# PMSM_500W_Controller_DC.net
KiCad netlist of a schematic drawn in Altium Designer
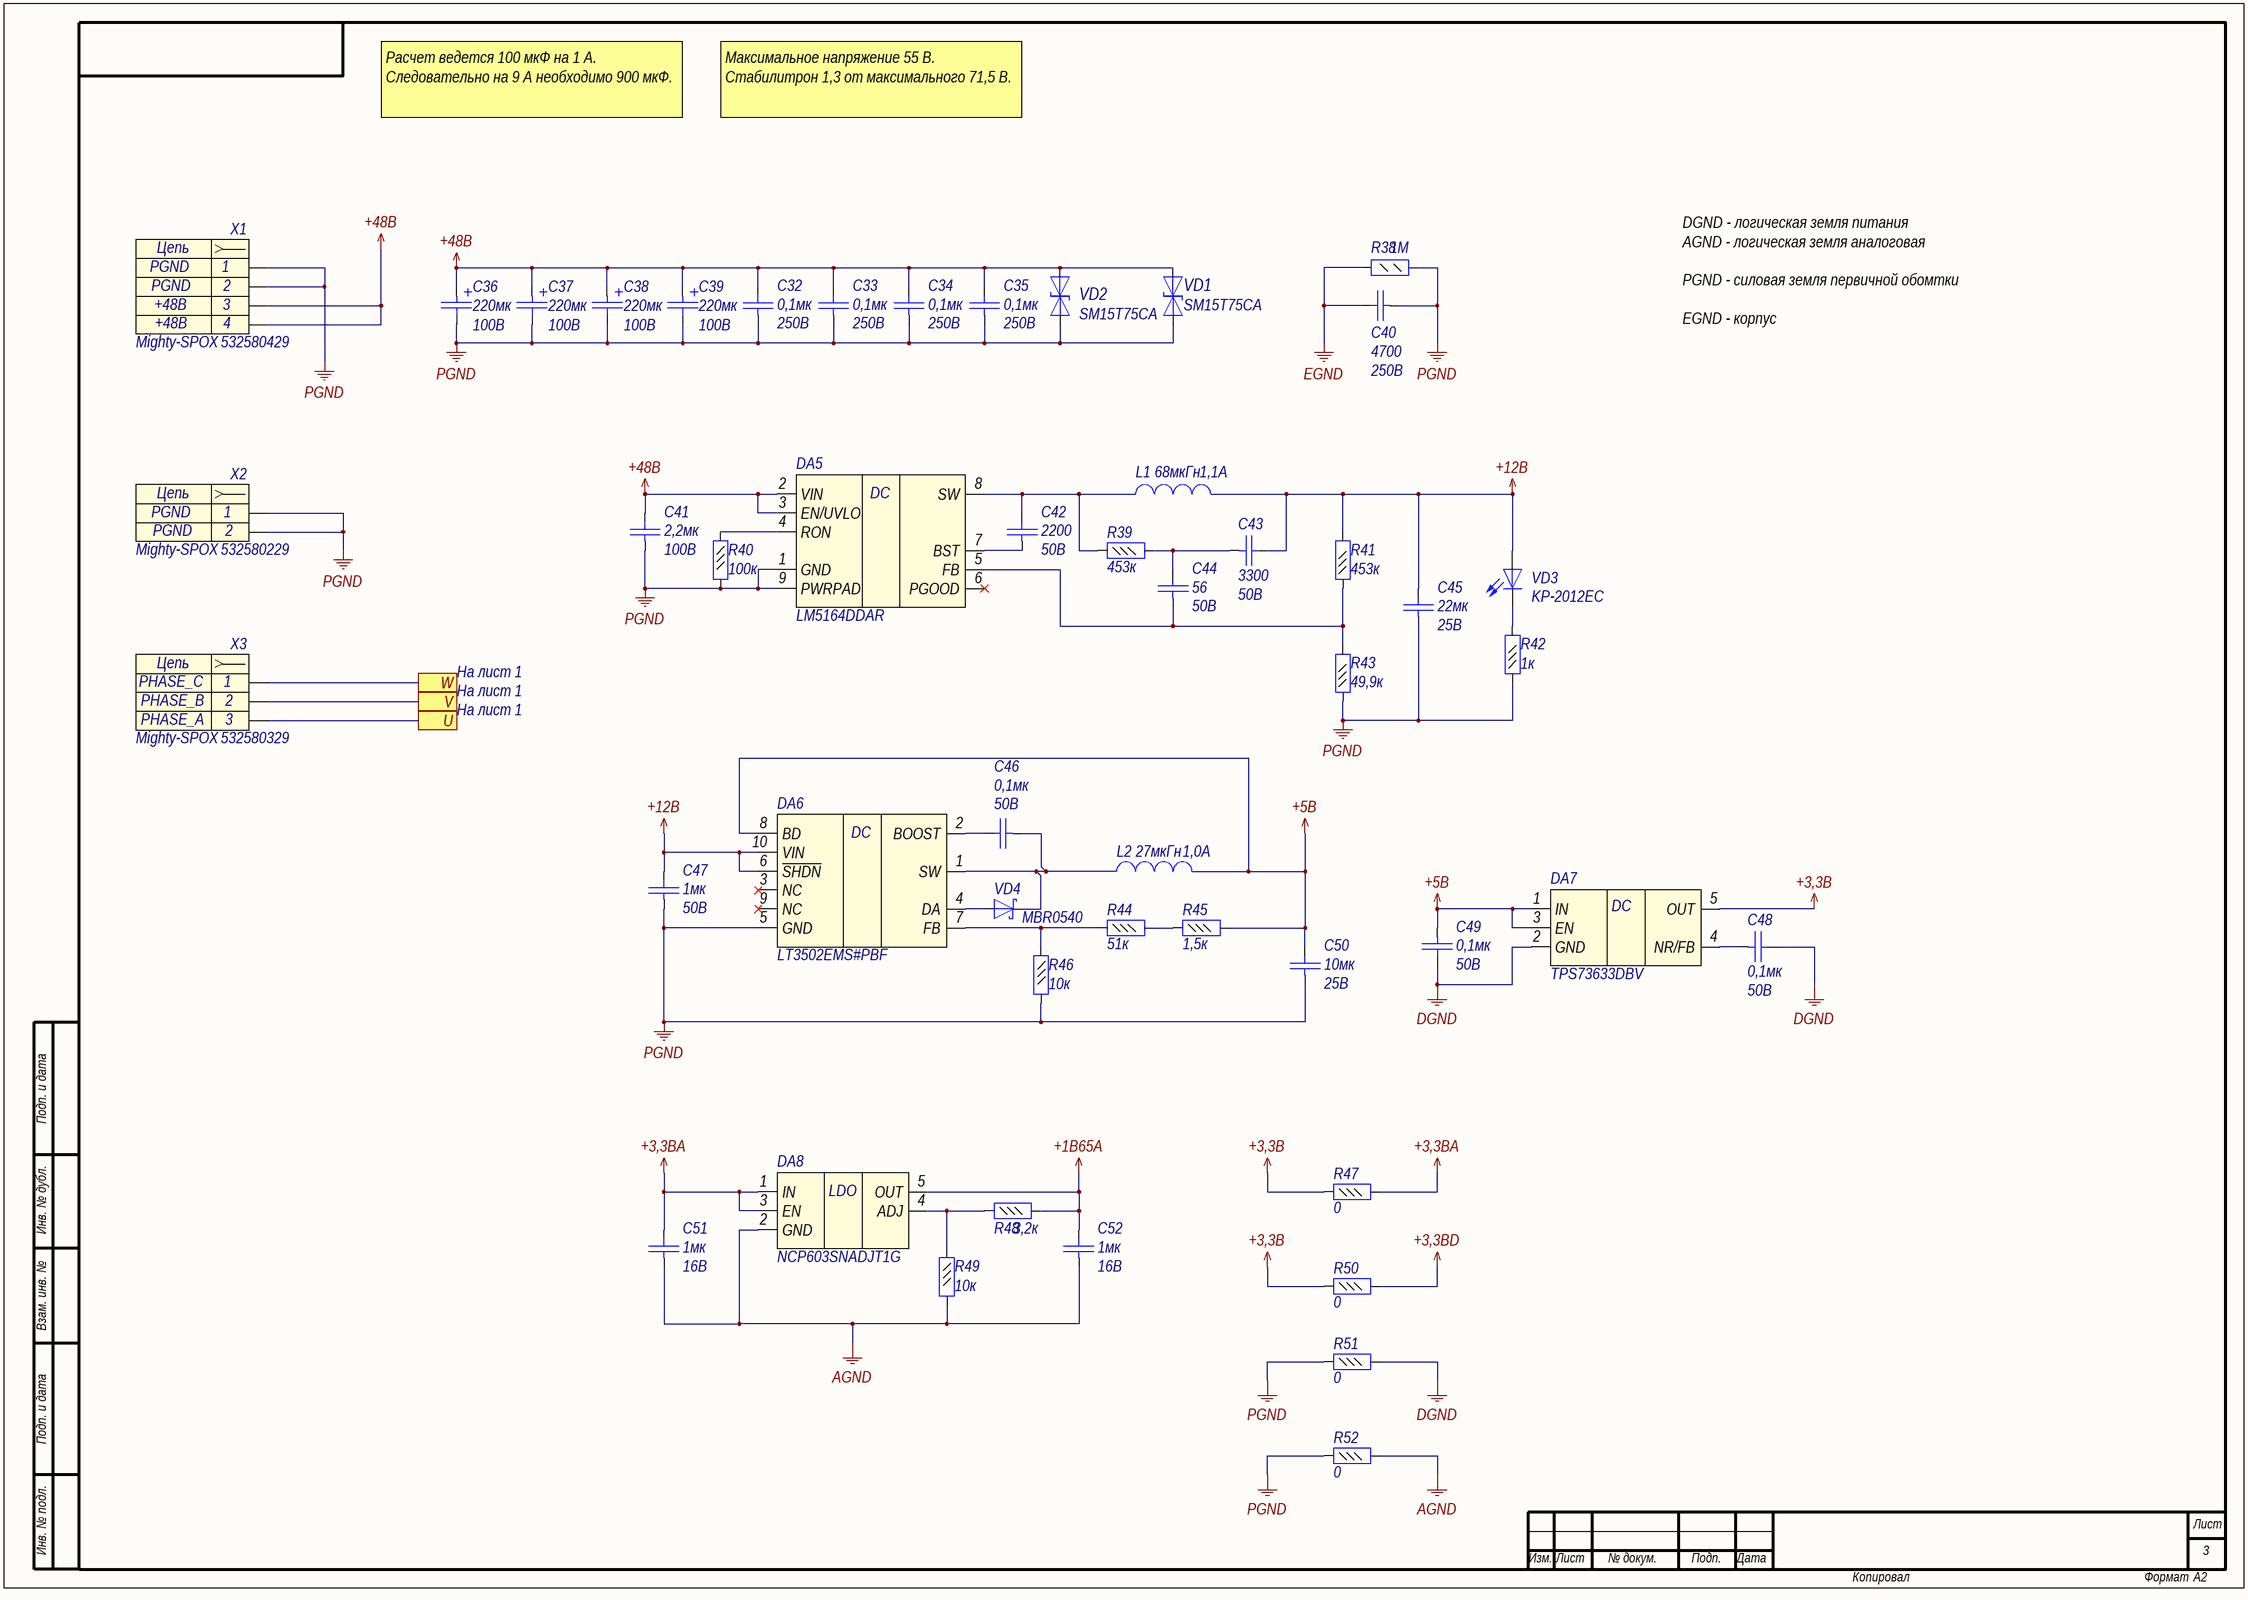
[diagram p0: PMSM_500W_Controller_DC.SchDoc]

(export (version "E")
  (design (tool "Eeschema 10.0.6"))
  (components
    (comp (ref "C32")
      (value "0,1мк")
      (footprint "C1206")
      (description "Конденсатор")
      (fields
        (field (name "VOLTAGE") "250В")
        (field (name "PART NUMBER") "GRM31CR72E104K")
        (field (name "Comment") "Capacitor")
      )
      (libsource (lib "MOP44") (part "Capacitor"))
    )
    (comp (ref "C33")
      (value "0,1мк")
      (footprint "C1206")
      (description "Конденсатор")
      (fields
        (field (name "VOLTAGE") "250В")
        (field (name "PART NUMBER") "GRM31CR72E104K")
        (field (name "Comment") "Capacitor")
      )
      (libsource (lib "MOP44") (part "Capacitor"))
    )
    (comp (ref "C34")
      (value "0,1мк")
      (footprint "C1206")
      (description "Конденсатор")
      (fields
        (field (name "VOLTAGE") "250В")
        (field (name "PART NUMBER") "GRM31CR72E104K")
        (field (name "Comment") "Capacitor")
      )
      (libsource (lib "MOP44") (part "Capacitor"))
    )
    (comp (ref "C35")
      (value "0,1мк")
      (footprint "C1206")
      (description "Конденсатор")
      (fields
        (field (name "VOLTAGE") "250В")
        (field (name "PART NUMBER") "GRM31CR72E104K")
        (field (name "Comment") "Capacitor")
      )
      (libsource (lib "MOP44") (part "Capacitor"))
    )
    (comp (ref "C36")
      (value "220мк")
      (footprint "K50-35(12.5X25)_V")
      (description "Конденсатор полярный")
      (fields
        (field (name "VOLTAGE") "100B")
        (field (name "PART NUMBER") "B41851A9227M000")
        (field (name "Comment") "Capacitor_pol")
      )
      (libsource (lib "MOP44") (part "Capacitor_pol"))
    )
    (comp (ref "C37")
      (value "220мк")
      (footprint "K50-35(12.5X25)_V")
      (description "Конденсатор полярный")
      (fields
        (field (name "VOLTAGE") "100B")
        (field (name "PART NUMBER") "B41851A9227M000")
        (field (name "Comment") "Capacitor_pol")
      )
      (libsource (lib "MOP44") (part "Capacitor_pol"))
    )
    (comp (ref "C38")
      (value "220мк")
      (footprint "K50-35(12.5X25)_V")
      (description "Конденсатор полярный")
      (fields
        (field (name "VOLTAGE") "100B")
        (field (name "PART NUMBER") "B41851A9227M000")
        (field (name "Comment") "Capacitor_pol")
      )
      (libsource (lib "MOP44") (part "Capacitor_pol"))
    )
    (comp (ref "C39")
      (value "220мк")
      (footprint "K50-35(12.5X25)_V")
      (description "Конденсатор полярный")
      (fields
        (field (name "VOLTAGE") "100B")
        (field (name "PART NUMBER") "B41851A9227M000")
        (field (name "Comment") "Capacitor_pol")
      )
      (libsource (lib "MOP44") (part "Capacitor_pol"))
    )
    (comp (ref "C40")
      (value "4700")
      (footprint "C0805")
      (description "Конденсатор")
      (fields
        (field (name "VOLTAGE") "250В")
        (field (name "PART NUMBER") "GRM21AR72E472KW")
        (field (name "Comment") "Capacitor")
      )
      (libsource (lib "MOP44") (part "Capacitor"))
    )
    (comp (ref "C41")
      (value "2,2мк")
      (footprint "C1210")
      (description "Конденсатор")
      (fields (field (name "VOLTAGE") "100В") (field (name "PART NUMBER") "GCJ32DR72A225KA01L"))
      (libsource (lib "MOP44") (part "Capacitor"))
    )
    (comp (ref "C42")
      (value "2200")
      (footprint "C0402")
      (description "Конденсатор")
      (fields
        (field (name "VOLTAGE") "50B")
        (field (name "PART NUMBER") "GRM155R71H222K")
        (field (name "Comment") "Capacitor")
      )
      (libsource (lib "MOP44") (part "Capacitor"))
    )
    (comp (ref "C43")
      (value "3300")
      (footprint "C0402")
      (description "Конденсатор")
      (fields
        (field (name "VOLTAGE") "50В")
        (field (name "PART NUMBER") "GRM155R71H332KA01D")
        (field (name "Comment") "Capacitor")
      )
      (libsource (lib "MOP44") (part "Capacitor"))
    )
    (comp (ref "C44")
      (value "56")
      (footprint "C0402")
      (description "Конденсатор")
      (fields
        (field (name "VOLTAGE") "50B")
        (field (name "PART NUMBER") "GRM1555C1H560J*")
        (field (name "Comment") "Capacitor")
      )
      (libsource (lib "MOP44") (part "Capacitor"))
    )
    (comp (ref "C45")
      (value "22мк")
      (footprint "C1210")
      (description "Конденсатор")
      (fields
        (field (name "VOLTAGE") "25B")
        (field (name "PART NUMBER") "TMK325B7226KMHT")
        (field (name "Comment") "Capacitor")
      )
      (libsource (lib "MOP44") (part "Capacitor"))
    )
    (comp (ref "C46")
      (value "0,1мк")
      (footprint "C0402")
      (description "Конденсатор")
      (fields
        (field (name "VOLTAGE") "50В")
        (field (name "PART NUMBER") "GRM155R71H104KE14D")
        (field (name "Comment") "Capacitor")
      )
      (libsource (lib "MOP44") (part "Capacitor"))
    )
    (comp (ref "C47")
      (value "1мк")
      (footprint "C0805")
      (description "Конденсатор")
      (fields
        (field (name "VOLTAGE") "50B")
        (field (name "PART NUMBER") "GRM21BR71H105K")
        (field (name "Comment") "Capacitor")
      )
      (libsource (lib "MOP44") (part "Capacitor"))
    )
    (comp (ref "C48")
      (value "0,1мк")
      (footprint "C0402")
      (description "Конденсатор")
      (fields
        (field (name "VOLTAGE") "50В")
        (field (name "PART NUMBER") "GRM155R71H104KE14D")
        (field (name "Comment") "Capacitor")
      )
      (libsource (lib "MOP44") (part "Capacitor"))
    )
    (comp (ref "C49")
      (value "0,1мк")
      (footprint "C0402")
      (description "Конденсатор")
      (fields
        (field (name "VOLTAGE") "50В")
        (field (name "PART NUMBER") "GRM155R71H104KE14D")
        (field (name "Comment") "Capacitor")
      )
      (libsource (lib "MOP44") (part "Capacitor"))
    )
    (comp (ref "C50")
      (value "10мк")
      (footprint "C1206")
      (description "Конденсатор")
      (fields
        (field (name "VOLTAGE") "25В")
        (field (name "PART NUMBER") "GRM31CR71E106KA12L*")
        (field (name "Comment") "Capacitor")
      )
      (libsource (lib "MOP44") (part "Capacitor"))
    )
    (comp (ref "C51")
      (value "1мк")
      (footprint "C0603")
      (description "Конденсатор")
      (fields
        (field (name "VOLTAGE") "16B")
        (field (name "PART NUMBER") "GRM188R71C105KA12D**")
        (field (name "Comment") "Capacitor")
      )
      (libsource (lib "MOP44") (part "Capacitor"))
    )
    (comp (ref "C52")
      (value "1мк")
      (footprint "C0603")
      (description "Конденсатор")
      (fields
        (field (name "VOLTAGE") "16B")
        (field (name "PART NUMBER") "GRM188R71C105KA12D**")
        (field (name "Comment") "Capacitor")
      )
      (libsource (lib "MOP44") (part "Capacitor"))
    )
    (comp (ref "DA5")
      (value "LM5164")
      (footprint "SO Powerpad8")
      (description "1-A synchronous buck DC/DC converter with ultra-low IQ")
      (fields (field (name "PART NUMBER") "LM5164DDAR") (field (name "MANUFACTURER") "Texas Instruments"))
      (libsource (lib "MOP44") (part "LM5164"))
    )
    (comp (ref "DA6")
      (value "LT3502_MS")
      (footprint "MSOP10")
      (description "1.1MHz/2.2MHz, 500mA  Step-Down Regulators")
      (fields (field (name "PART NUMBER") "LT3502EMS#PBF") (field (name "MANUFACTURER") "Linear Technology"))
      (libsource (lib "MOP44") (part "LT3502_MS"))
    )
    (comp (ref "DA7")
      (value "TPS736DBV")
      (footprint "SOT23-5")
      (description "400-mA Low-Dropout Regulator with Reverse Current  Protection")
      (fields (field (name "PART NUMBER") "TPS73633DBV") (field (name "MANUFACTURER") "Texas Instruments"))
      (libsource (lib "MOP44") (part "TPS736DBV"))
    )
    (comp (ref "DA8")
      (value "NCP603")
      (footprint "TSOP5")
      (description "High Performance  CMOS LDO Regulator with  Enable and Enhanced ESD  Protection")
      (fields (field (name "PART NUMBER") "NCP603SNADJT1G") (field (name "MANUFACTURER") "ON Semiconductor"))
      (libsource (lib "MOP44") (part "NCP603"))
    )
    (comp (ref "L1")
      (value "68мкГн")
      (footprint "SDR1006")
      (description "EMI Suppression Filter")
      (fields
        (field (name "RATED CURRENT") "1,1A")
        (field (name "PART NUMBER") "SDR1006- 680KL")
        (field (name "Comment") "Inductor")
      )
      (libsource (lib "MOP44") (part "Inductor"))
    )
    (comp (ref "L2")
      (value "27мкГн")
      (footprint "SDR0604")
      (description "EMI Suppression Filter")
      (fields
        (field (name "RATED CURRENT") "1,0A")
        (field (name "PART NUMBER") "SDR0604- 270YL")
        (field (name "Comment") "Inductor")
      )
      (libsource (lib "MOP44") (part "Inductor"))
    )
    (comp (ref "R38")
      (value "1М")
      (footprint "R0805")
      (description "Резистор")
      (fields (field (name "PART NUMBER") "RC0805FR-071ML") (field (name "POWER") "0,125Вт"))
      (libsource (lib "MOP44") (part "Resistor_0,125Вт"))
    )
    (comp (ref "R39")
      (value "453к")
      (footprint "R0402")
      (description "Резистор")
      (fields (field (name "PART NUMBER") "RC0402FR-07453KL") (field (name "POWER") "0,062Вт"))
      (libsource (lib "") (part "Resistor_0,062Вт_1"))
    )
    (comp (ref "R40")
      (value "100к")
      (footprint "R0402")
      (description "Резистор")
      (fields (field (name "PART NUMBER") "RC0402FR-07100KL") (field (name "POWER") "0,062Вт"))
      (libsource (lib "MOP44") (part "Resistor_0,062Вт"))
    )
    (comp (ref "R41")
      (value "453к")
      (footprint "R0402")
      (description "Резистор")
      (fields (field (name "PART NUMBER") "RC0402FR-07453KL") (field (name "POWER") "0,062Вт"))
      (libsource (lib "") (part "Resistor_0,062Вт_2"))
    )
    (comp (ref "R42")
      (value "1к")
      (footprint "R0402")
      (description "Резистор")
      (fields (field (name "PART NUMBER") "RC0402FR-071KL") (field (name "POWER") "0,062Вт"))
      (libsource (lib "") (part "Resistor_0,062Вт_2"))
    )
    (comp (ref "R43")
      (value "49,9к")
      (footprint "R0402")
      (description "Резистор")
      (fields (field (name "PART NUMBER") "RC0402FR-0749K9L") (field (name "POWER") "0,062Вт"))
      (libsource (lib "") (part "Resistor_0,062Вт_2"))
    )
    (comp (ref "R44")
      (value "51к")
      (footprint "R0402")
      (description "Резистор")
      (fields (field (name "PART NUMBER") "RC0402FR-0751KL") (field (name "POWER") "0,062Вт"))
      (libsource (lib "") (part "Resistor_0,062Вт_1"))
    )
    (comp (ref "R45")
      (value "1,5к")
      (footprint "R0402")
      (description "Резистор")
      (fields (field (name "PART NUMBER") "RC0402FR-071K5") (field (name "POWER") "0,062Вт"))
      (libsource (lib "") (part "Resistor_0,062Вт_1"))
    )
    (comp (ref "R46")
      (value "10к")
      (footprint "R0402")
      (description "Резистор")
      (fields (field (name "PART NUMBER") "RC0402FR-0710KL") (field (name "POWER") "0,062Вт"))
      (libsource (lib "MOP44") (part "Resistor_0,062Вт"))
    )
    (comp (ref "R47")
      (value "0")
      (footprint "R0603")
      (description "Резистор")
      (fields (field (name "PART NUMBER") "RC0603FR-070RL") (field (name "POWER") "0,062Вт"))
      (libsource (lib "") (part "Resistor_0,062Вт_1"))
    )
    (comp (ref "R48")
      (value "3,2к")
      (footprint "R0402")
      (description "Резистор")
      (fields (field (name "PART NUMBER") "RT0402BRD073K2L") (field (name "POWER") "0,062Вт"))
      (libsource (lib "") (part "Resistor_0,062Вт_1"))
    )
    (comp (ref "R49")
      (value "10к")
      (footprint "R0402")
      (description "Резистор")
      (fields (field (name "PART NUMBER") "RC0402FR-0710KL") (field (name "POWER") "0,062Вт"))
      (libsource (lib "MOP44") (part "Resistor_0,062Вт"))
    )
    (comp (ref "R50")
      (value "0")
      (footprint "R0603")
      (description "Резистор")
      (fields (field (name "PART NUMBER") "RC0603FR-070RL") (field (name "POWER") "0,062Вт"))
      (libsource (lib "") (part "Resistor_0,062Вт_1"))
    )
    (comp (ref "R51")
      (value "0")
      (footprint "R0603")
      (description "Резистор")
      (fields (field (name "PART NUMBER") "RC0603FR-070RL") (field (name "POWER") "0,062Вт"))
      (libsource (lib "") (part "Resistor_0,062Вт_1"))
    )
    (comp (ref "R52")
      (value "0")
      (footprint "R0603")
      (description "Резистор")
      (fields (field (name "PART NUMBER") "RC0603FR-070RL") (field (name "POWER") "0,062Вт"))
      (libsource (lib "") (part "Resistor_0,062Вт_1"))
    )
    (comp (ref "VD1")
      (value "DiodeZenerDual")
      (footprint "SMC")
      (description "Cтабилитрон (диод выпрямительный лавинный) двусторонний")
      (fields (field (name "PART NUMBER") "SM15T75CA"))
      (libsource (lib "MOP44") (part "DiodeZenerDual"))
    )
    (comp (ref "VD2")
      (value "DiodeZenerDual")
      (footprint "SMC")
      (description "Cтабилитрон (диод выпрямительный лавинный) двусторонний")
      (fields (field (name "PART NUMBER") "SM15T75CA"))
      (libsource (lib "MOP44") (part "DiodeZenerDual"))
    )
    (comp (ref "VD3")
      (value "LED")
      (footprint "L_0805")
      (description "Светодиод")
      (fields (field (name "PART NUMBER") "KP-2012EC"))
      (libsource (lib "MOP44") (part "LED"))
    )
    (comp (ref "VD4")
      (value "DiodeSchottky")
      (footprint "SOD-123")
      (description "Диод Шоттки")
      (fields (field (name "PART NUMBER") "MBR0540"))
      (libsource (lib "MOP44") (part "DiodeSchottky"))
    )
    (comp (ref "X1")
      (value "Header_4_sct")
      (footprint "MOLEX_532580429")
      (description "Разъем - 4 конт. розетка")
      (fields (field (name "PART NAME") "Mighty-SPOX") (field (name "PART NUMBER") "532580429"))
      (libsource (lib "MOP44") (part "Header_4_sct"))
    )
    (comp (ref "X2")
      (value "Header_2_sct")
      (footprint "MOLEX_532580229")
      (description "Разъем - 2 конт. розетка")
      (fields (field (name "PART NAME") "Mighty-SPOX") (field (name "PART NUMBER") "532580229"))
      (libsource (lib "MOP44") (part "Header_2_sct"))
    )
    (comp (ref "X3")
      (value "Header_3_sct")
      (footprint "MOLEX_532580329")
      (description "Разъем - 3 конт. розетка")
      (fields (field (name "PART NAME") "Mighty-SPOX") (field (name "PART NUMBER") "532580329"))
      (libsource (lib "MOP44") (part "Header_3_sct"))
    )
  )
  (nets
    (net (code "1") (name "+1B65A") (class "Default")
      (node (ref "C52") (pin "2") (pinfunction "2_2") (pintype "passive"))
      (node (ref "DA8") (pin "5") (pinfunction "OUT_5") (pintype "power_in"))
      (node (ref "R48") (pin "2") (pinfunction "2_2") (pintype "passive"))
    )
    (net (code "2") (name "+3,3B") (class "Default")
      (node (ref "DA7") (pin "5") (pinfunction "OUT_5") (pintype "power_in"))
      (node (ref "R47") (pin "1") (pinfunction "1_1") (pintype "passive"))
      (node (ref "R50") (pin "1") (pinfunction "1_1") (pintype "passive"))
    )
    (net (code "3") (name "+3,3BA") (class "Default")
      (node (ref "C51") (pin "2") (pinfunction "2_2") (pintype "passive"))
      (node (ref "DA8") (pin "1") (pinfunction "IN_1") (pintype "power_in"))
      (node (ref "DA8") (pin "3") (pinfunction "EN_3") (pintype "power_in"))
      (node (ref "R47") (pin "2") (pinfunction "2_2") (pintype "passive"))
    )
    (net (code "4") (name "+3,3BD") (class "Default")
      (node (ref "R50") (pin "2") (pinfunction "2_2") (pintype "passive"))
    )
    (net (code "5") (name "+5B") (class "Default")
      (node (ref "C49") (pin "1") (pinfunction "1_1") (pintype "passive"))
      (node (ref "C50") (pin "2") (pinfunction "2_2") (pintype "passive"))
      (node (ref "DA6") (pin "8") (pinfunction "BD_8") (pintype "power_in"))
      (node (ref "DA7") (pin "1") (pinfunction "IN_1") (pintype "power_in"))
      (node (ref "DA7") (pin "3") (pinfunction "EN_3") (pintype "power_in"))
      (node (ref "L2") (pin "2") (pinfunction "2_2") (pintype "passive"))
      (node (ref "R45") (pin "2") (pinfunction "2_2") (pintype "passive"))
    )
    (net (code "6") (name "+12B") (class "Default")
      (node (ref "C43") (pin "2") (pinfunction "2_2") (pintype "passive"))
      (node (ref "C45") (pin "2") (pinfunction "2_2") (pintype "passive"))
      (node (ref "C47") (pin "2") (pinfunction "2_2") (pintype "passive"))
      (node (ref "DA6") (pin "10") (pinfunction "VIN_10") (pintype "power_in"))
      (node (ref "DA6") (pin "6") (pinfunction "~{SHDN}_6") (pintype "power_in"))
      (node (ref "L1") (pin "2") (pinfunction "2_2") (pintype "passive"))
      (node (ref "R41") (pin "2") (pinfunction "2_2") (pintype "passive"))
      (node (ref "VD3") (pin "2") (pinfunction "A_2") (pintype "passive"))
    )
    (net (code "7") (name "+48B") (class "Default")
      (node (ref "C32") (pin "2") (pinfunction "2_2") (pintype "passive"))
      (node (ref "C33") (pin "2") (pinfunction "2_2") (pintype "passive"))
      (node (ref "C34") (pin "2") (pinfunction "2_2") (pintype "passive"))
      (node (ref "C35") (pin "2") (pinfunction "2_2") (pintype "passive"))
      (node (ref "C36") (pin "1") (pinfunction "1_1") (pintype "passive"))
      (node (ref "C37") (pin "1") (pinfunction "1_1") (pintype "passive"))
      (node (ref "C38") (pin "1") (pinfunction "1_1") (pintype "passive"))
      (node (ref "C39") (pin "1") (pinfunction "1_1") (pintype "passive"))
      (node (ref "C41") (pin "2") (pinfunction "2_2") (pintype "passive"))
      (node (ref "DA5") (pin "2") (pinfunction "VIN_2") (pintype "power_in"))
      (node (ref "DA5") (pin "3") (pinfunction "EN/UVLO_3") (pintype "power_in"))
      (node (ref "VD1") (pin "1") (pinfunction "K_1") (pintype "passive"))
      (node (ref "VD2") (pin "2") (pinfunction "A_2") (pintype "passive"))
      (node (ref "X1") (pin "3") (pinfunction "3_3") (pintype "passive"))
      (node (ref "X1") (pin "4") (pinfunction "4_4") (pintype "passive"))
    )
    (net (code "8") (name "/U") (class "Default")
      (node (ref "X3") (pin "3") (pinfunction "3_3") (pintype "passive"))
    )
    (net (code "9") (name "/V") (class "Default")
      (node (ref "X3") (pin "2") (pinfunction "2_2") (pintype "passive"))
    )
    (net (code "10") (name "/W") (class "Default")
      (node (ref "X3") (pin "1") (pinfunction "1_1") (pintype "passive"))
    )
    (net (code "11") (name "AGND") (class "Default")
      (node (ref "C51") (pin "1") (pinfunction "1_1") (pintype "passive"))
      (node (ref "C52") (pin "1") (pinfunction "1_1") (pintype "passive"))
      (node (ref "DA8") (pin "2") (pinfunction "GND_2") (pintype "power_in"))
      (node (ref "R49") (pin "2") (pinfunction "2_2") (pintype "passive"))
      (node (ref "R52") (pin "2") (pinfunction "2_2") (pintype "passive"))
    )
    (net (code "12") (name "DGND") (class "Default")
      (node (ref "C48") (pin "2") (pinfunction "2_2") (pintype "passive"))
      (node (ref "C49") (pin "2") (pinfunction "2_2") (pintype "passive"))
      (node (ref "DA7") (pin "2") (pinfunction "GND_2") (pintype "power_in"))
      (node (ref "R51") (pin "2") (pinfunction "2_2") (pintype "passive"))
    )
    (net (code "13") (name "EGND") (class "Default")
      (node (ref "C40") (pin "2") (pinfunction "2_2") (pintype "passive"))
      (node (ref "R38") (pin "2") (pinfunction "2_2") (pintype "passive"))
    )
    (net (code "14") (name "Net-(C43-Pad1)") (class "Default")
      (node (ref "C43") (pin "1") (pinfunction "1_1") (pintype "passive"))
      (node (ref "C44") (pin "2") (pinfunction "2_2") (pintype "passive"))
      (node (ref "R39") (pin "2") (pinfunction "2_2") (pintype "passive"))
    )
    (net (code "15") (name "Net-(DA5-BST)") (class "Default")
      (node (ref "C42") (pin "1") (pinfunction "1_1") (pintype "passive"))
      (node (ref "DA5") (pin "7") (pinfunction "BST_7") (pintype "power_in"))
    )
    (net (code "16") (name "Net-(DA5-FB)") (class "Default")
      (node (ref "C44") (pin "1") (pinfunction "1_1") (pintype "passive"))
      (node (ref "DA5") (pin "5") (pinfunction "FB_5") (pintype "power_in"))
      (node (ref "R41") (pin "1") (pinfunction "1_1") (pintype "passive"))
      (node (ref "R43") (pin "2") (pinfunction "2_2") (pintype "passive"))
    )
    (net (code "17") (name "Net-(DA5-RON)") (class "Default")
      (node (ref "DA5") (pin "4") (pinfunction "RON_4") (pintype "power_in"))
      (node (ref "R40") (pin "1") (pinfunction "1_1") (pintype "passive"))
    )
    (net (code "18") (name "Net-(DA5-SW)") (class "Default")
      (node (ref "C42") (pin "2") (pinfunction "2_2") (pintype "passive"))
      (node (ref "DA5") (pin "8") (pinfunction "SW_8") (pintype "power_in"))
      (node (ref "L1") (pin "1") (pinfunction "1_1") (pintype "passive"))
      (node (ref "R39") (pin "1") (pinfunction "1_1") (pintype "passive"))
    )
    (net (code "19") (name "Net-(DA6-BOOST)") (class "Default")
      (node (ref "C46") (pin "2") (pinfunction "2_2") (pintype "passive"))
      (node (ref "DA6") (pin "2") (pinfunction "BOOST_2") (pintype "power_in"))
    )
    (net (code "20") (name "Net-(DA6-DA)") (class "Default")
      (node (ref "DA6") (pin "4") (pinfunction "DA_4") (pintype "power_in"))
      (node (ref "VD4") (pin "2") (pinfunction "A_2") (pintype "passive"))
    )
    (net (code "21") (name "Net-(DA6-FB)") (class "Default")
      (node (ref "DA6") (pin "7") (pinfunction "FB_7") (pintype "power_in"))
      (node (ref "R44") (pin "1") (pinfunction "1_1") (pintype "passive"))
      (node (ref "R46") (pin "1") (pinfunction "1_1") (pintype "passive"))
    )
    (net (code "22") (name "Net-(DA6-SW)") (class "Default")
      (node (ref "C46") (pin "1") (pinfunction "1_1") (pintype "passive"))
      (node (ref "DA6") (pin "1") (pinfunction "SW_1") (pintype "power_in"))
      (node (ref "L2") (pin "1") (pinfunction "1_1") (pintype "passive"))
      (node (ref "VD4") (pin "1") (pinfunction "K_1") (pintype "passive"))
    )
    (net (code "23") (name "Net-(DA7-NR{slash}FB)") (class "Default")
      (node (ref "C48") (pin "1") (pinfunction "1_1") (pintype "passive"))
      (node (ref "DA7") (pin "4") (pinfunction "NR/FB_4") (pintype "power_in"))
    )
    (net (code "24") (name "Net-(DA8-ADJ)") (class "Default")
      (node (ref "DA8") (pin "4") (pinfunction "ADJ_4") (pintype "power_in"))
      (node (ref "R48") (pin "1") (pinfunction "1_1") (pintype "passive"))
      (node (ref "R49") (pin "1") (pinfunction "1_1") (pintype "passive"))
    )
    (net (code "25") (name "Net-(R44-Pad2)") (class "Default")
      (node (ref "R44") (pin "2") (pinfunction "2_2") (pintype "passive"))
      (node (ref "R45") (pin "1") (pinfunction "1_1") (pintype "passive"))
    )
    (net (code "26") (name "Net-(VD3-K)") (class "Default")
      (node (ref "R42") (pin "2") (pinfunction "2_2") (pintype "passive"))
      (node (ref "VD3") (pin "1") (pinfunction "K_1") (pintype "passive"))
    )
    (net (code "27") (name "PGND") (class "Default")
      (node (ref "C32") (pin "1") (pinfunction "1_1") (pintype "passive"))
      (node (ref "C33") (pin "1") (pinfunction "1_1") (pintype "passive"))
      (node (ref "C34") (pin "1") (pinfunction "1_1") (pintype "passive"))
      (node (ref "C35") (pin "1") (pinfunction "1_1") (pintype "passive"))
      (node (ref "C36") (pin "2") (pinfunction "2_2") (pintype "passive"))
      (node (ref "C37") (pin "2") (pinfunction "2_2") (pintype "passive"))
      (node (ref "C38") (pin "2") (pinfunction "2_2") (pintype "passive"))
      (node (ref "C39") (pin "2") (pinfunction "2_2") (pintype "passive"))
      (node (ref "C40") (pin "1") (pinfunction "1_1") (pintype "passive"))
      (node (ref "C41") (pin "1") (pinfunction "1_1") (pintype "passive"))
      (node (ref "C45") (pin "1") (pinfunction "1_1") (pintype "passive"))
      (node (ref "C47") (pin "1") (pinfunction "1_1") (pintype "passive"))
      (node (ref "C50") (pin "1") (pinfunction "1_1") (pintype "passive"))
      (node (ref "DA5") (pin "1") (pinfunction "GND_1") (pintype "power_in"))
      (node (ref "DA5") (pin "9") (pinfunction "PWRPAD_9") (pintype "power_in"))
      (node (ref "DA6") (pin "5") (pinfunction "GND_5") (pintype "power_in"))
      (node (ref "R38") (pin "1") (pinfunction "1_1") (pintype "passive"))
      (node (ref "R40") (pin "2") (pinfunction "2_2") (pintype "passive"))
      (node (ref "R42") (pin "1") (pinfunction "1_1") (pintype "passive"))
      (node (ref "R43") (pin "1") (pinfunction "1_1") (pintype "passive"))
      (node (ref "R46") (pin "2") (pinfunction "2_2") (pintype "passive"))
      (node (ref "R51") (pin "1") (pinfunction "1_1") (pintype "passive"))
      (node (ref "R52") (pin "1") (pinfunction "1_1") (pintype "passive"))
      (node (ref "VD1") (pin "2") (pinfunction "A_2") (pintype "passive"))
      (node (ref "VD2") (pin "1") (pinfunction "K_1") (pintype "passive"))
      (node (ref "X1") (pin "1") (pinfunction "1_1") (pintype "passive"))
      (node (ref "X1") (pin "2") (pinfunction "2_2") (pintype "passive"))
      (node (ref "X2") (pin "1") (pinfunction "1_1") (pintype "passive"))
      (node (ref "X2") (pin "2") (pinfunction "2_2") (pintype "passive"))
    )
    (net (code "28") (name "unconnected-(DA5-PGOOD-Pad6)") (class "Default")
      (node (ref "DA5") (pin "6") (pinfunction "PGOOD_6") (pintype "power_in+no_connect"))
    )
    (net (code "29") (name "unconnected-(DA6-NC-Pad3)") (class "Default")
      (node (ref "DA6") (pin "3") (pinfunction "NC_3") (pintype "power_in+no_connect"))
    )
    (net (code "30") (name "unconnected-(DA6-NC-Pad9)") (class "Default")
      (node (ref "DA6") (pin "9") (pinfunction "NC_9") (pintype "power_in+no_connect"))
    )
  )
)
